# 2_4.net
KiCad netlist of a schematic drawn in Altium Designer
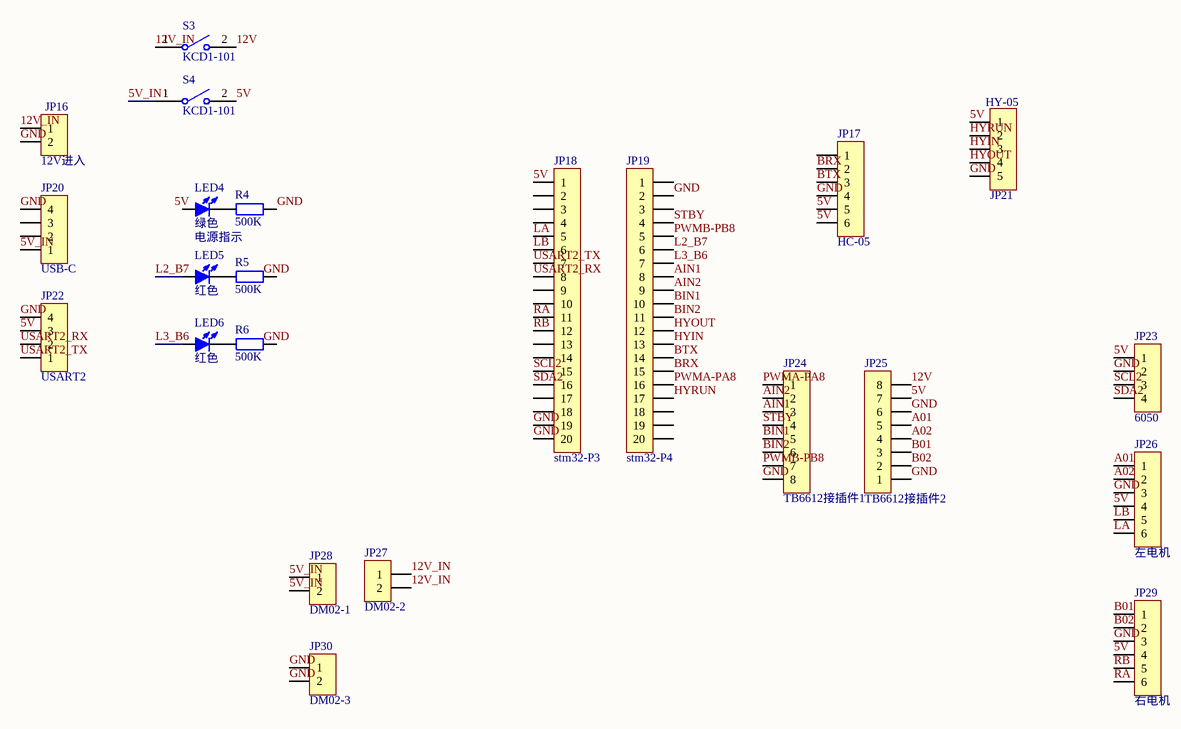
[diagram p0: 2.4.SchDoc]

(export (version "E")
  (design (tool "Eeschema 10.0.6"))
  (components
    (comp (ref "JP16")
      (value "HDR-1X2")
      (footprint "KF2EDGK5.08-LI-2P")
      (description "2P接插件")
      (fields (field (name "BOM名称") "12V进入") (field (name "版权归属") "源创客"))
      (libsource (lib "5.8 - 接插件-脚距5.08 (200mil) ") (part "Header 2"))
    )
    (comp (ref "JP17")
      (value "HC-05")
      (footprint "HDR2.54-M-LI-6P")
      (description "6P接插件")
      (fields (field (name "BOM名称") "HC-05") (field (name "版权归属") "封装库来自淘宝 ID：黄晶宝石"))
      (libsource (lib "5.3 - 接插件-脚距2.54 (100mil) ") (part "Header 6"))
    )
    (comp (ref "JP18")
      (value "HDR-1X20")
      (footprint "HDR2.54-M-LI-20P")
      (description "20P接插件")
      (fields (field (name "BOM名称") "stm32-P3") (field (name "版权归属") "封装库来自淘宝 ID：黄晶宝石"))
      (libsource (lib "5.3 - 接插件-脚距2.54 (100mil) ") (part "Header 20"))
    )
    (comp (ref "JP19")
      (value "HDR-1X20")
      (footprint "HDR2.54-M-LI-20P")
      (description "20P接插件")
      (fields (field (name "BOM名称") "stm32-P4") (field (name "版权归属") "封装库来自淘宝 ID：黄晶宝石"))
      (libsource (lib "") (part "Header 20_1"))
    )
    (comp (ref "JP20")
      (value "HDR-1X4")
      (footprint "HDR2.54-M-LI-4P")
      (description "4P接插件")
      (fields (field (name "BOM名称") "USB-C") (field (name "版权归属") "封装库来自淘宝 ID：黄晶宝石"))
      (libsource (lib "5.3 - 接插件-脚距2.54 (100mil) ") (part "Header 4"))
    )
    (comp (ref "JP21")
      (value "HY-05")
      (footprint "HDR2.54-M-LI-5P")
      (description "5P接插件")
      (fields (field (name "版权归属") "封装库来自淘宝 ID：黄晶宝石"))
      (libsource (lib "5.3 - 接插件-脚距2.54 (100mil) ") (part "Header 5"))
    )
    (comp (ref "JP22")
      (value "HDR-1X4")
      (footprint "HDR2.54-M-LI-4P")
      (description "4P接插件")
      (fields (field (name "BOM名称") "USART2") (field (name "版权归属") "封装库来自淘宝 ID：黄晶宝石"))
      (libsource (lib "5.3 - 接插件-脚距2.54 (100mil) ") (part "Header 4"))
    )
    (comp (ref "JP23")
      (value "HDR-1X4")
      (footprint "HDR2.54-M-LI-4P")
      (description "4P接插件")
      (fields (field (name "BOM名称") "6050") (field (name "版权归属") "封装库来自淘宝 ID：黄晶宝石"))
      (libsource (lib "") (part "Header 4_1"))
    )
    (comp (ref "JP24")
      (value "HDR-1X8")
      (footprint "HDR2.54-M-LI-8P")
      (description "8P接插件")
      (fields (field (name "BOM名称") "TB6612接插件1") (field (name "版权归属") "封装库来自淘宝 ID：黄晶宝石"))
      (libsource (lib "5.3 - 接插件-脚距2.54 (100mil) ") (part "Header 8"))
    )
    (comp (ref "JP25")
      (value "HDR-1X8")
      (footprint "HDR2.54-M-LI-8P")
      (description "8P接插件")
      (fields (field (name "BOM名称") "TB6612接插件2") (field (name "版权归属") "封装库来自淘宝 ID：黄晶宝石"))
      (libsource (lib "") (part "Header 8_1"))
    )
    (comp (ref "JP26")
      (value "HDR-1X6")
      (footprint "KF128-5.08-6P")
      (description "6P接插件")
      (fields (field (name "BOM名称") "左电机") (field (name "版权归属") "源创客"))
      (libsource (lib "5.8 - 接插件-脚距5.08 (200mil) ") (part "Header 6"))
    )
    (comp (ref "JP27")
      (value "HDR-1X2")
      (footprint "HDR2.54-M-LI-2P")
      (description "2P接插件")
      (fields (field (name "BOM名称") "DM02-2") (field (name "版权归属") "封装库来自淘宝 ID：黄晶宝石"))
      (libsource (lib "") (part "Header 2_1"))
    )
    (comp (ref "JP28")
      (value "HDR-1X2")
      (footprint "HDR2.54-M-LI-2P")
      (description "2P接插件")
      (fields (field (name "BOM名称") "DM02-1") (field (name "版权归属") "封装库来自淘宝 ID：黄晶宝石"))
      (libsource (lib "5.3 - 接插件-脚距2.54 (100mil) ") (part "Header 2"))
    )
    (comp (ref "JP29")
      (value "HDR-1X6")
      (footprint "KF128-5.08-6P")
      (description "6P接插件")
      (fields (field (name "BOM名称") "右电机") (field (name "版权归属") "源创客"))
      (libsource (lib "5.8 - 接插件-脚距5.08 (200mil) ") (part "Header 6"))
    )
    (comp (ref "JP30")
      (value "HDR-1X2")
      (footprint "HDR2.54-M-LI-2P")
      (description "2P接插件")
      (fields (field (name "BOM名称") "DM02-3") (field (name "版权归属") "封装库来自淘宝 ID：黄晶宝石"))
      (libsource (lib "5.3 - 接插件-脚距2.54 (100mil) ") (part "Header 2"))
    )
    (comp (ref "LED4")
      (value "绿色")
      (footprint "LED 0805G")
      (description "贴片LED")
      (fields (field (name "BOM名称") "电源指示") (field (name "版权归属") "源创客"))
      (libsource (lib "LED") (part "LED-SMD"))
    )
    (comp (ref "LED5")
      (value "红色")
      (footprint "LED 0805G")
      (description "贴片LED")
      (fields (field (name "版权归属") "源创客"))
      (libsource (lib "LED") (part "LED-SMD"))
    )
    (comp (ref "LED6")
      (value "红色")
      (footprint "LED 0805G")
      (description "贴片LED")
      (fields (field (name "版权归属") "源创客"))
      (libsource (lib "LED") (part "LED-SMD"))
    )
    (comp (ref "R4")
      (value "500K")
      (footprint "R 0805_M")
      (description "贴片电阻")
      (fields (field (name "版权归属") "来自淘宝 ID：黄晶宝石"))
      (libsource (lib "0.1 - 电阻-电容-电感") (part "R"))
    )
    (comp (ref "R5")
      (value "500K")
      (footprint "R 0805_M")
      (description "贴片电阻")
      (fields (field (name "版权归属") "来自淘宝 ID：黄晶宝石"))
      (libsource (lib "0.1 - 电阻-电容-电感") (part "R"))
    )
    (comp (ref "R6")
      (value "500K")
      (footprint "R 0805_M")
      (description "贴片电阻")
      (fields (field (name "版权归属") "来自淘宝 ID：黄晶宝石"))
      (libsource (lib "0.1 - 电阻-电容-电感") (part "R"))
    )
    (comp (ref "S3")
      (value "KCD1-101")
      (footprint "KCD1-101")
      (description "1路单刀船型开关")
      (fields (field (name "版权归属") "封装库来自淘宝 ID：黄晶宝石"))
      (libsource (lib "0.7 - 常用按键-开关") (part "KCD1-101"))
    )
    (comp (ref "S4")
      (value "KCD1-101")
      (footprint "KCD1-101")
      (description "1路单刀船型开关")
      (fields (field (name "版权归属") "封装库来自淘宝 ID：黄晶宝石"))
      (libsource (lib "0.7 - 常用按键-开关") (part "KCD1-101"))
    )
  )
  (nets
    (net (code "1") (name "/5V") (class "Default")
      (node (ref "JP17") (pin "5") (pinfunction "5_5") (pintype "passive"))
      (node (ref "JP17") (pin "6") (pinfunction "6_6") (pintype "passive"))
      (node (ref "JP18") (pin "1") (pinfunction "1_1") (pintype "passive"))
      (node (ref "JP21") (pin "1") (pinfunction "1_1") (pintype "passive"))
      (node (ref "JP22") (pin "3") (pinfunction "3_3") (pintype "passive"))
      (node (ref "JP23") (pin "1") (pinfunction "1_1") (pintype "passive"))
      (node (ref "JP25") (pin "7") (pinfunction "7_7") (pintype "passive"))
      (node (ref "JP26") (pin "4") (pinfunction "4_4") (pintype "passive"))
      (node (ref "JP29") (pin "4") (pinfunction "4_4") (pintype "passive"))
      (node (ref "LED4") (pin "1") (pinfunction "A_1") (pintype "passive"))
      (node (ref "S4") (pin "2") (pinfunction "2_2") (pintype "passive"))
    )
    (net (code "2") (name "/5V_IN") (class "Default")
      (node (ref "JP20") (pin "1") (pinfunction "1_1") (pintype "passive"))
      (node (ref "JP28") (pin "1") (pinfunction "1_1") (pintype "passive"))
      (node (ref "JP28") (pin "2") (pinfunction "2_2") (pintype "passive"))
      (node (ref "S4") (pin "1") (pinfunction "1_1") (pintype "passive"))
    )
    (net (code "3") (name "/12V") (class "Default")
      (node (ref "JP25") (pin "8") (pinfunction "8_8") (pintype "passive"))
      (node (ref "S3") (pin "2") (pinfunction "2_2") (pintype "passive"))
    )
    (net (code "4") (name "/12V_IN") (class "Default")
      (node (ref "JP16") (pin "1") (pinfunction "1_1") (pintype "passive"))
      (node (ref "JP27") (pin "1") (pinfunction "1_1") (pintype "passive"))
      (node (ref "JP27") (pin "2") (pinfunction "2_2") (pintype "passive"))
      (node (ref "S3") (pin "1") (pinfunction "1_1") (pintype "passive"))
    )
    (net (code "5") (name "/A01") (class "Default")
      (node (ref "JP25") (pin "5") (pinfunction "5_5") (pintype "passive"))
      (node (ref "JP26") (pin "1") (pinfunction "1_1") (pintype "passive"))
    )
    (net (code "6") (name "/A02") (class "Default")
      (node (ref "JP25") (pin "4") (pinfunction "4_4") (pintype "passive"))
      (node (ref "JP26") (pin "2") (pinfunction "2_2") (pintype "passive"))
    )
    (net (code "7") (name "/AIN1") (class "Default")
      (node (ref "JP19") (pin "8") (pinfunction "8_8") (pintype "passive"))
      (node (ref "JP24") (pin "3") (pinfunction "3_3") (pintype "passive"))
    )
    (net (code "8") (name "/AIN2") (class "Default")
      (node (ref "JP19") (pin "9") (pinfunction "9_9") (pintype "passive"))
      (node (ref "JP24") (pin "2") (pinfunction "2_2") (pintype "passive"))
    )
    (net (code "9") (name "/B01") (class "Default")
      (node (ref "JP25") (pin "3") (pinfunction "3_3") (pintype "passive"))
      (node (ref "JP29") (pin "1") (pinfunction "1_1") (pintype "passive"))
    )
    (net (code "10") (name "/B02") (class "Default")
      (node (ref "JP25") (pin "2") (pinfunction "2_2") (pintype "passive"))
      (node (ref "JP29") (pin "2") (pinfunction "2_2") (pintype "passive"))
    )
    (net (code "11") (name "/BIN1") (class "Default")
      (node (ref "JP19") (pin "10") (pinfunction "10_10") (pintype "passive"))
      (node (ref "JP24") (pin "5") (pinfunction "5_5") (pintype "passive"))
    )
    (net (code "12") (name "/BIN2") (class "Default")
      (node (ref "JP19") (pin "11") (pinfunction "11_11") (pintype "passive"))
      (node (ref "JP24") (pin "6") (pinfunction "6_6") (pintype "passive"))
    )
    (net (code "13") (name "/BRX") (class "Default")
      (node (ref "JP17") (pin "2") (pinfunction "2_2") (pintype "passive"))
      (node (ref "JP19") (pin "15") (pinfunction "15_15") (pintype "passive"))
    )
    (net (code "14") (name "/BTX") (class "Default")
      (node (ref "JP17") (pin "3") (pinfunction "3_3") (pintype "passive"))
      (node (ref "JP19") (pin "14") (pinfunction "14_14") (pintype "passive"))
    )
    (net (code "15") (name "/GND") (class "Default")
      (node (ref "JP16") (pin "2") (pinfunction "2_2") (pintype "passive"))
      (node (ref "JP17") (pin "4") (pinfunction "4_4") (pintype "passive"))
      (node (ref "JP18") (pin "19") (pinfunction "19_19") (pintype "passive"))
      (node (ref "JP18") (pin "20") (pinfunction "20_20") (pintype "passive"))
      (node (ref "JP19") (pin "2") (pinfunction "2_2") (pintype "passive"))
      (node (ref "JP20") (pin "4") (pinfunction "4_4") (pintype "passive"))
      (node (ref "JP21") (pin "5") (pinfunction "5_5") (pintype "passive"))
      (node (ref "JP22") (pin "4") (pinfunction "4_4") (pintype "passive"))
      (node (ref "JP23") (pin "2") (pinfunction "2_2") (pintype "passive"))
      (node (ref "JP24") (pin "8") (pinfunction "8_8") (pintype "passive"))
      (node (ref "JP25") (pin "1") (pinfunction "1_1") (pintype "passive"))
      (node (ref "JP25") (pin "6") (pinfunction "6_6") (pintype "passive"))
      (node (ref "JP26") (pin "3") (pinfunction "3_3") (pintype "passive"))
      (node (ref "JP29") (pin "3") (pinfunction "3_3") (pintype "passive"))
      (node (ref "JP30") (pin "1") (pinfunction "1_1") (pintype "passive"))
      (node (ref "JP30") (pin "2") (pinfunction "2_2") (pintype "passive"))
      (node (ref "R4") (pin "2") (pinfunction "2_2") (pintype "passive"))
      (node (ref "R5") (pin "2") (pinfunction "2_2") (pintype "passive"))
      (node (ref "R6") (pin "2") (pinfunction "2_2") (pintype "passive"))
    )
    (net (code "16") (name "/HYIN") (class "Default")
      (node (ref "JP19") (pin "13") (pinfunction "13_13") (pintype "passive"))
      (node (ref "JP21") (pin "3") (pinfunction "3_3") (pintype "passive"))
    )
    (net (code "17") (name "/HYOUT") (class "Default")
      (node (ref "JP19") (pin "12") (pinfunction "12_12") (pintype "passive"))
      (node (ref "JP21") (pin "4") (pinfunction "4_4") (pintype "passive"))
    )
    (net (code "18") (name "/HYRUN") (class "Default")
      (node (ref "JP19") (pin "17") (pinfunction "17_17") (pintype "passive"))
      (node (ref "JP21") (pin "2") (pinfunction "2_2") (pintype "passive"))
    )
    (net (code "19") (name "/L2_B7") (class "Default")
      (node (ref "JP19") (pin "6") (pinfunction "6_6") (pintype "passive"))
      (node (ref "LED5") (pin "1") (pinfunction "A_1") (pintype "passive"))
    )
    (net (code "20") (name "/L3_B6") (class "Default")
      (node (ref "JP19") (pin "7") (pinfunction "7_7") (pintype "passive"))
      (node (ref "LED6") (pin "1") (pinfunction "A_1") (pintype "passive"))
    )
    (net (code "21") (name "/LA") (class "Default")
      (node (ref "JP18") (pin "5") (pinfunction "5_5") (pintype "passive"))
      (node (ref "JP26") (pin "6") (pinfunction "6_6") (pintype "passive"))
    )
    (net (code "22") (name "/LB") (class "Default")
      (node (ref "JP18") (pin "6") (pinfunction "6_6") (pintype "passive"))
      (node (ref "JP26") (pin "5") (pinfunction "5_5") (pintype "passive"))
    )
    (net (code "23") (name "/PWMA-PA8") (class "Default")
      (node (ref "JP19") (pin "16") (pinfunction "16_16") (pintype "passive"))
      (node (ref "JP24") (pin "1") (pinfunction "1_1") (pintype "passive"))
    )
    (net (code "24") (name "/PWMB-PB8") (class "Default")
      (node (ref "JP19") (pin "5") (pinfunction "5_5") (pintype "passive"))
      (node (ref "JP24") (pin "7") (pinfunction "7_7") (pintype "passive"))
    )
    (net (code "25") (name "/RA") (class "Default")
      (node (ref "JP18") (pin "11") (pinfunction "11_11") (pintype "passive"))
      (node (ref "JP29") (pin "6") (pinfunction "6_6") (pintype "passive"))
    )
    (net (code "26") (name "/RB") (class "Default")
      (node (ref "JP18") (pin "12") (pinfunction "12_12") (pintype "passive"))
      (node (ref "JP29") (pin "5") (pinfunction "5_5") (pintype "passive"))
    )
    (net (code "27") (name "/SCL2") (class "Default")
      (node (ref "JP18") (pin "15") (pinfunction "15_15") (pintype "passive"))
      (node (ref "JP23") (pin "3") (pinfunction "3_3") (pintype "passive"))
    )
    (net (code "28") (name "/SDA2") (class "Default")
      (node (ref "JP18") (pin "16") (pinfunction "16_16") (pintype "passive"))
      (node (ref "JP23") (pin "4") (pinfunction "4_4") (pintype "passive"))
    )
    (net (code "29") (name "/STBY") (class "Default")
      (node (ref "JP19") (pin "4") (pinfunction "4_4") (pintype "passive"))
      (node (ref "JP24") (pin "4") (pinfunction "4_4") (pintype "passive"))
    )
    (net (code "30") (name "/USART2_RX") (class "Default")
      (node (ref "JP18") (pin "8") (pinfunction "8_8") (pintype "passive"))
      (node (ref "JP22") (pin "2") (pinfunction "2_2") (pintype "passive"))
    )
    (net (code "31") (name "/USART2_TX") (class "Default")
      (node (ref "JP18") (pin "7") (pinfunction "7_7") (pintype "passive"))
      (node (ref "JP22") (pin "1") (pinfunction "1_1") (pintype "passive"))
    )
    (net (code "32") (name "Net-(LED4-K)") (class "Default")
      (node (ref "LED4") (pin "2") (pinfunction "K_2") (pintype "passive"))
      (node (ref "R4") (pin "1") (pinfunction "1_1") (pintype "passive"))
    )
    (net (code "33") (name "Net-(LED5-K)") (class "Default")
      (node (ref "LED5") (pin "2") (pinfunction "K_2") (pintype "passive"))
      (node (ref "R5") (pin "1") (pinfunction "1_1") (pintype "passive"))
    )
    (net (code "34") (name "Net-(LED6-K)") (class "Default")
      (node (ref "LED6") (pin "2") (pinfunction "K_2") (pintype "passive"))
      (node (ref "R6") (pin "1") (pinfunction "1_1") (pintype "passive"))
    )
    (net (code "35") (name "unconnected-(JP17-Pad1)") (class "Default")
      (node (ref "JP17") (pin "1") (pinfunction "1_1") (pintype "passive"))
    )
    (net (code "36") (name "unconnected-(JP18-Pad2)") (class "Default")
      (node (ref "JP18") (pin "2") (pinfunction "2_2") (pintype "passive"))
    )
    (net (code "37") (name "unconnected-(JP18-Pad3)") (class "Default")
      (node (ref "JP18") (pin "3") (pinfunction "3_3") (pintype "passive"))
    )
    (net (code "38") (name "unconnected-(JP18-Pad4)") (class "Default")
      (node (ref "JP18") (pin "4") (pinfunction "4_4") (pintype "passive"))
    )
    (net (code "39") (name "unconnected-(JP18-Pad9)") (class "Default")
      (node (ref "JP18") (pin "9") (pinfunction "9_9") (pintype "passive"))
    )
    (net (code "40") (name "unconnected-(JP18-Pad10)") (class "Default")
      (node (ref "JP18") (pin "10") (pinfunction "10_10") (pintype "passive"))
    )
    (net (code "41") (name "unconnected-(JP18-Pad13)") (class "Default")
      (node (ref "JP18") (pin "13") (pinfunction "13_13") (pintype "passive"))
    )
    (net (code "42") (name "unconnected-(JP18-Pad14)") (class "Default")
      (node (ref "JP18") (pin "14") (pinfunction "14_14") (pintype "passive"))
    )
    (net (code "43") (name "unconnected-(JP18-Pad17)") (class "Default")
      (node (ref "JP18") (pin "17") (pinfunction "17_17") (pintype "passive"))
    )
    (net (code "44") (name "unconnected-(JP18-Pad18)") (class "Default")
      (node (ref "JP18") (pin "18") (pinfunction "18_18") (pintype "passive"))
    )
    (net (code "45") (name "unconnected-(JP19-Pad1)") (class "Default")
      (node (ref "JP19") (pin "1") (pinfunction "1_1") (pintype "passive"))
    )
    (net (code "46") (name "unconnected-(JP19-Pad3)") (class "Default")
      (node (ref "JP19") (pin "3") (pinfunction "3_3") (pintype "passive"))
    )
    (net (code "47") (name "unconnected-(JP19-Pad18)") (class "Default")
      (node (ref "JP19") (pin "18") (pinfunction "18_18") (pintype "passive"))
    )
    (net (code "48") (name "unconnected-(JP19-Pad19)") (class "Default")
      (node (ref "JP19") (pin "19") (pinfunction "19_19") (pintype "passive"))
    )
    (net (code "49") (name "unconnected-(JP19-Pad20)") (class "Default")
      (node (ref "JP19") (pin "20") (pinfunction "20_20") (pintype "passive"))
    )
    (net (code "50") (name "unconnected-(JP20-Pad2)") (class "Default")
      (node (ref "JP20") (pin "2") (pinfunction "2_2") (pintype "passive"))
    )
    (net (code "51") (name "unconnected-(JP20-Pad3)") (class "Default")
      (node (ref "JP20") (pin "3") (pinfunction "3_3") (pintype "passive"))
    )
  )
)
